# pecs_storm.net
KiCad netlist of a schematic drawn in EAGLE
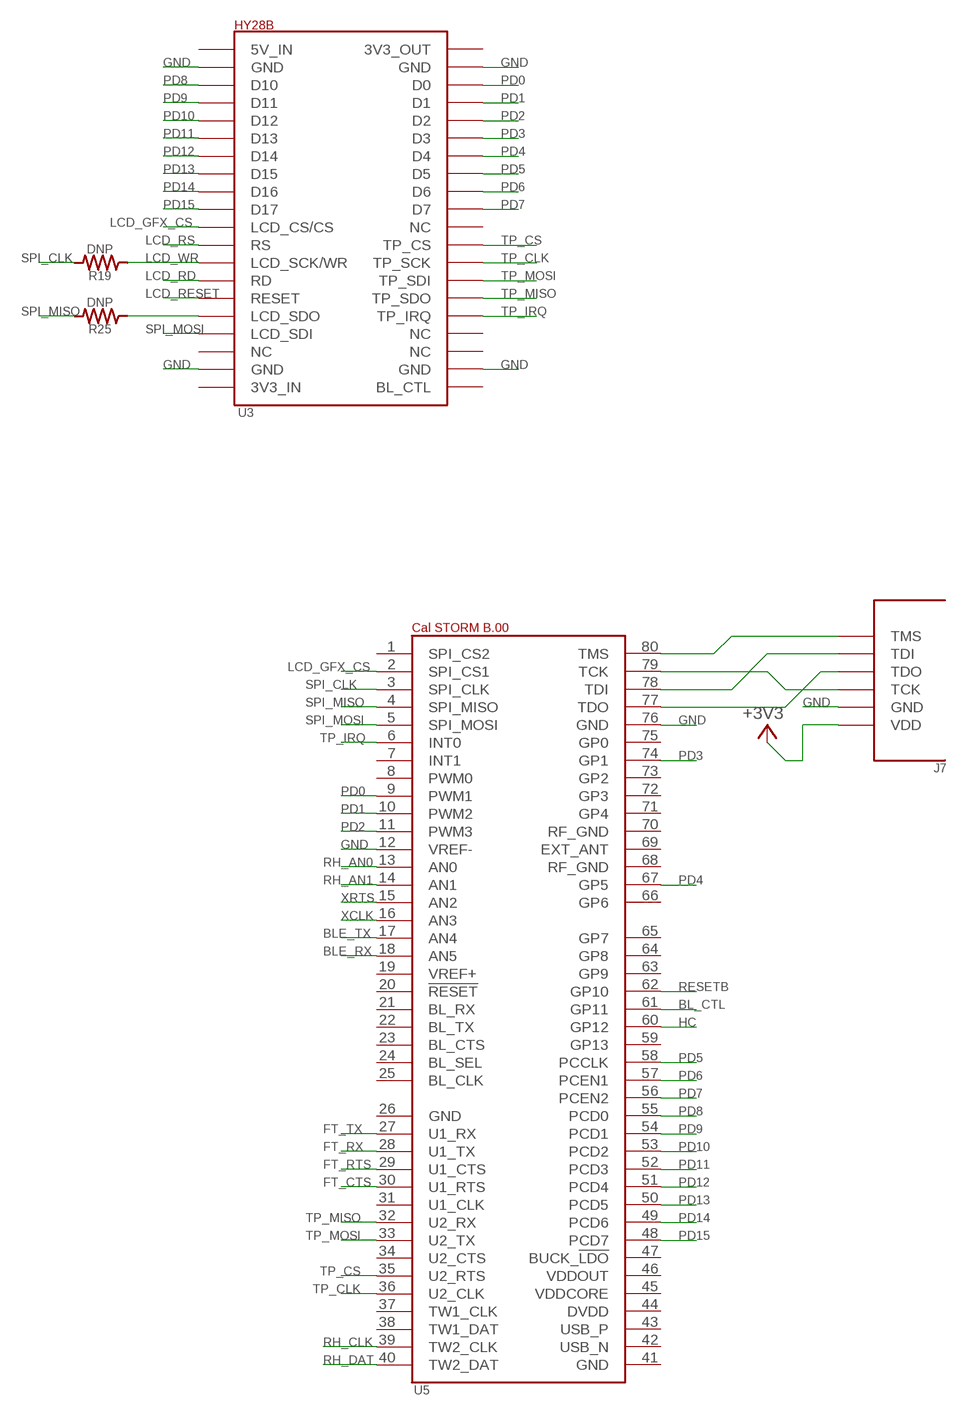
[diagram p0: schematic, sheet 1, part 1 of 2]
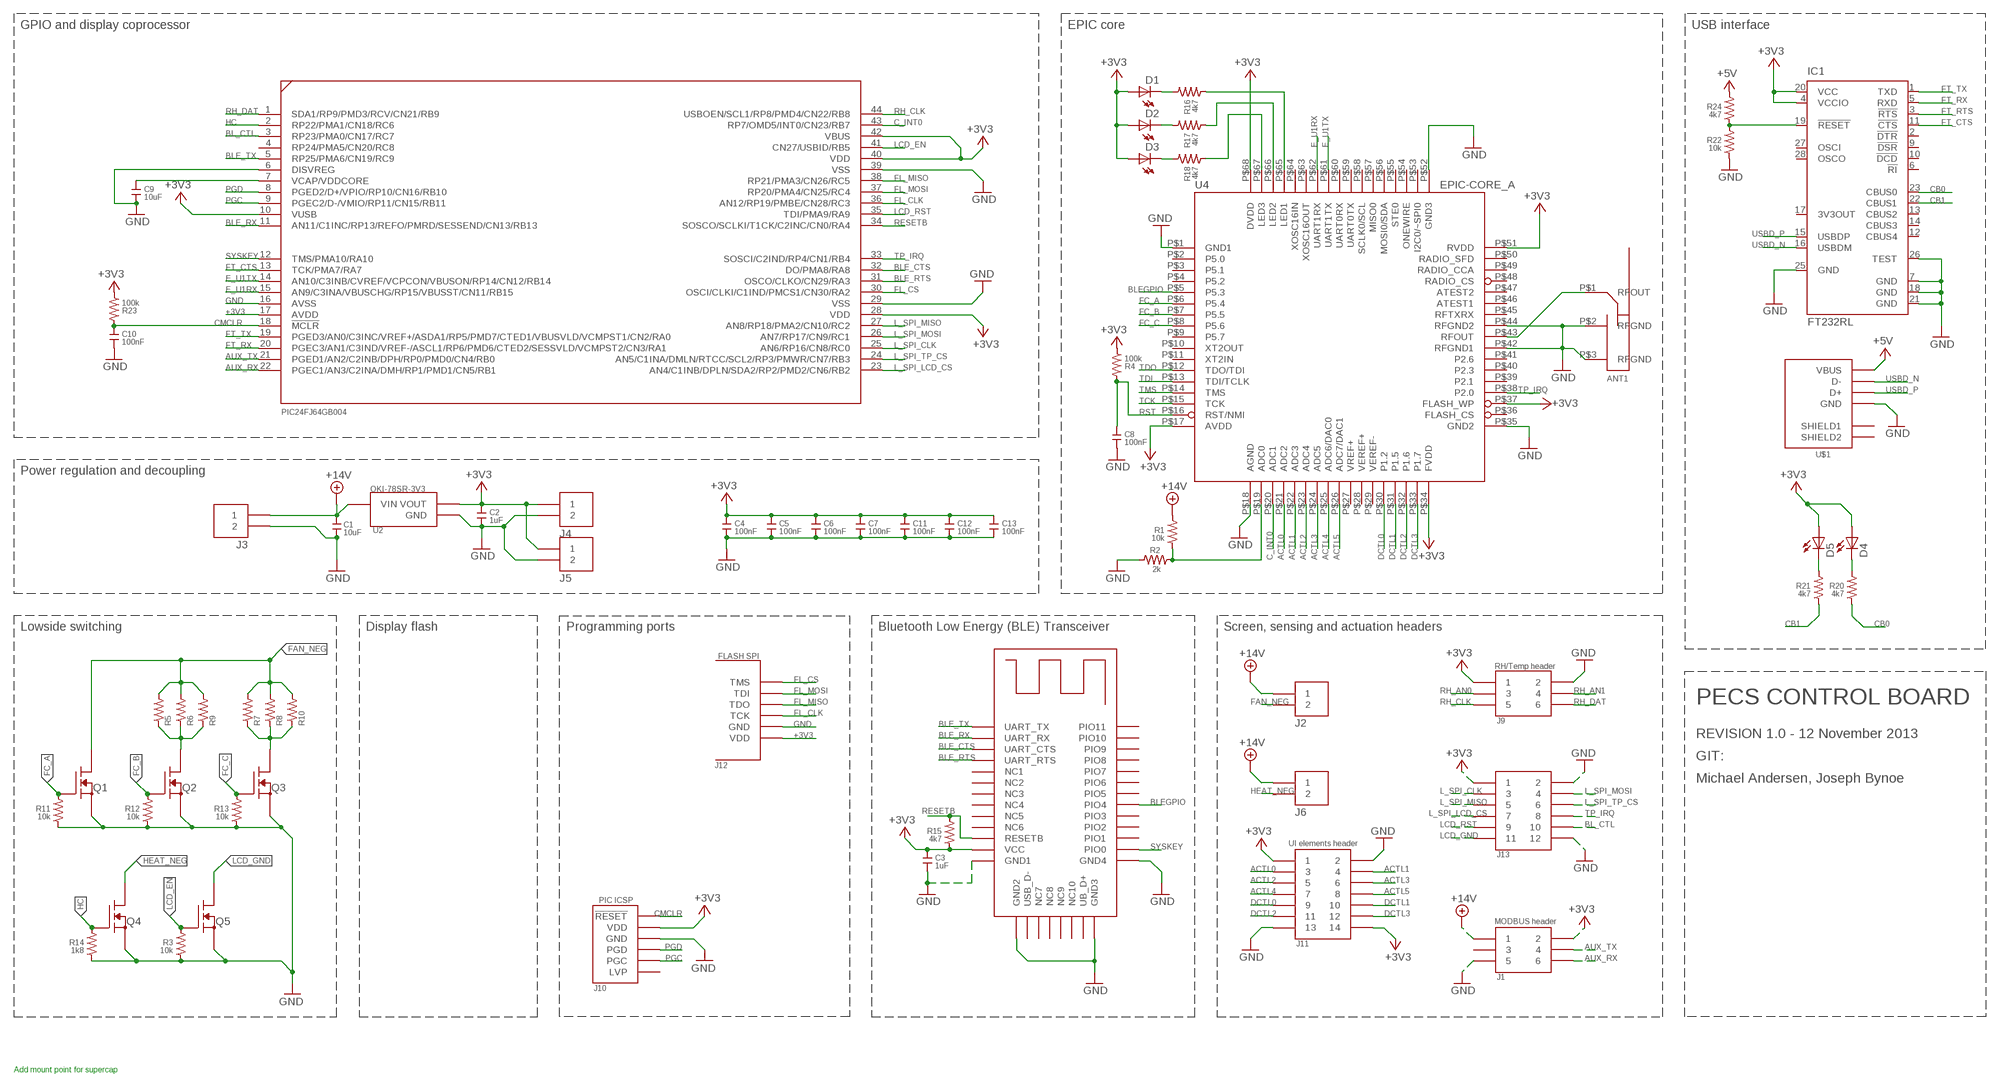
[diagram p1: schematic, sheet 1, part 2 of 2]

(export (version "E")
  (design (tool "Eeschema 10.0.6"))
  (components
    (comp (ref "ANT1")
      (value "PIFA-2.4GHZ")
      (footprint "eagle-import:PIFA-2.4GHZ")
      (libsource (lib "eagle-import") (part "PIFA-2.4GHZ"))
    )
    (comp (ref "BLE1")
      (value "HM10_BLE")
      (footprint "eagle-import:HM10")
      (libsource (lib "eagle-import") (part "HM10_BLE"))
    )
    (comp (ref "C1")
      (value "10uF")
      (footprint "eagle-import:0805")
      (libsource (lib "eagle-import") (part "0805_CAPACITOR"))
    )
    (comp (ref "C2")
      (value "1uF")
      (footprint "eagle-import:0805")
      (libsource (lib "eagle-import") (part "0805_CAPACITOR"))
    )
    (comp (ref "C3")
      (value "1uF")
      (footprint "eagle-import:0805")
      (libsource (lib "eagle-import") (part "0805_CAPACITOR"))
    )
    (comp (ref "C4")
      (value "100nF")
      (footprint "eagle-import:0805")
      (libsource (lib "eagle-import") (part "0805_CAPACITOR"))
    )
    (comp (ref "C5")
      (value "100nF")
      (footprint "eagle-import:0805")
      (libsource (lib "eagle-import") (part "0805_CAPACITOR"))
    )
    (comp (ref "C6")
      (value "100nF")
      (footprint "eagle-import:0805")
      (libsource (lib "eagle-import") (part "0805_CAPACITOR"))
    )
    (comp (ref "C7")
      (value "100nF")
      (footprint "eagle-import:0805")
      (libsource (lib "eagle-import") (part "0805_CAPACITOR"))
    )
    (comp (ref "C8")
      (value "100nF")
      (footprint "eagle-import:0805")
      (libsource (lib "eagle-import") (part "0805_CAPACITOR"))
    )
    (comp (ref "C9")
      (value "10uF")
      (footprint "eagle-import:0805")
      (libsource (lib "eagle-import") (part "0805_CAPACITOR"))
    )
    (comp (ref "C10")
      (value "100nF")
      (footprint "eagle-import:0805")
      (libsource (lib "eagle-import") (part "0805_CAPACITOR"))
    )
    (comp (ref "C11")
      (value "100nF")
      (footprint "eagle-import:0805")
      (libsource (lib "eagle-import") (part "0805_CAPACITOR"))
    )
    (comp (ref "C12")
      (value "100nF")
      (footprint "eagle-import:0805")
      (libsource (lib "eagle-import") (part "0805_CAPACITOR"))
    )
    (comp (ref "C13")
      (value "100nF")
      (footprint "eagle-import:0805")
      (libsource (lib "eagle-import") (part "0805_CAPACITOR"))
    )
    (comp (ref "D1")
      (value "LED1206")
      (footprint "eagle-import:LED-1206")
      (libsource (lib "eagle-import") (part "LED1206"))
    )
    (comp (ref "D2")
      (value "LED1206")
      (footprint "eagle-import:LED-1206")
      (libsource (lib "eagle-import") (part "LED1206"))
    )
    (comp (ref "D3")
      (value "LED1206")
      (footprint "eagle-import:LED-1206")
      (libsource (lib "eagle-import") (part "LED1206"))
    )
    (comp (ref "D4")
      (value "LED1206")
      (footprint "eagle-import:LED-1206")
      (libsource (lib "eagle-import") (part "LED1206"))
    )
    (comp (ref "D5")
      (value "LED1206")
      (footprint "eagle-import:LED-1206")
      (libsource (lib "eagle-import") (part "LED1206"))
    )
    (comp (ref "IC1")
      (value "FT232RL")
      (footprint "eagle-import:SSOP28")
      (libsource (lib "eagle-import") (part "FT232RL"))
    )
    (comp (ref "J1")
      (value "HD.1-6")
      (footprint "eagle-import:HD.1-6")
      (libsource (lib "eagle-import") (part "HD.1-6"))
    )
    (comp (ref "J2")
      (value "H.1-2")
      (footprint "eagle-import:H.1-2")
      (libsource (lib "eagle-import") (part "H.1-2"))
    )
    (comp (ref "J3")
      (value "H.1-2")
      (footprint "eagle-import:H.1-2")
      (libsource (lib "eagle-import") (part "H.1-2"))
    )
    (comp (ref "J4")
      (value "H.1-2")
      (footprint "eagle-import:H.1-2")
      (libsource (lib "eagle-import") (part "H.1-2"))
    )
    (comp (ref "J5")
      (value "H.1-2")
      (footprint "eagle-import:H.1-2")
      (libsource (lib "eagle-import") (part "H.1-2"))
    )
    (comp (ref "J6")
      (value "H.1-2")
      (footprint "eagle-import:H.1-2")
      (libsource (lib "eagle-import") (part "H.1-2"))
    )
    (comp (ref "J7")
      (value "JTAG")
      (footprint "eagle-import:JTAG")
      (libsource (lib "eagle-import") (part "JTAG"))
    )
    (comp (ref "J9")
      (value "HD.1-6")
      (footprint "eagle-import:HD.1-6")
      (libsource (lib "eagle-import") (part "HD.1-6"))
    )
    (comp (ref "J10")
      (value "ICSP_HDR")
      (footprint "eagle-import:H.1-6")
      (libsource (lib "eagle-import") (part "ICSP_HDR"))
    )
    (comp (ref "J11")
      (value "HD.1-14")
      (footprint "eagle-import:HD.1-16")
      (libsource (lib "eagle-import") (part "HD.1-14"))
    )
    (comp (ref "J12")
      (value "JTAG")
      (footprint "eagle-import:JTAG")
      (libsource (lib "eagle-import") (part "JTAG"))
    )
    (comp (ref "J13")
      (value "HD.1-12")
      (footprint "eagle-import:HD.1-12")
      (libsource (lib "eagle-import") (part "HD.1-12"))
    )
    (comp (ref "Q1")
      (value "NFET_DPAK")
      (footprint "eagle-import:DPAK")
      (libsource (lib "eagle-import") (part "NFET_DPAK"))
    )
    (comp (ref "Q2")
      (value "NFET_DPAK")
      (footprint "eagle-import:DPAK")
      (libsource (lib "eagle-import") (part "NFET_DPAK"))
    )
    (comp (ref "Q3")
      (value "NFET_DPAK")
      (footprint "eagle-import:DPAK")
      (libsource (lib "eagle-import") (part "NFET_DPAK"))
    )
    (comp (ref "Q4")
      (value "NFET_DPAK")
      (footprint "eagle-import:DPAK")
      (libsource (lib "eagle-import") (part "NFET_DPAK"))
    )
    (comp (ref "Q5")
      (value "NFET_DPAK")
      (footprint "eagle-import:DPAK")
      (libsource (lib "eagle-import") (part "NFET_DPAK"))
    )
    (comp (ref "R1")
      (value "10k")
      (footprint "eagle-import:0805")
      (libsource (lib "eagle-import") (part "0805_RESISTOR"))
    )
    (comp (ref "R2")
      (value "2k")
      (footprint "eagle-import:0805")
      (libsource (lib "eagle-import") (part "0805_RESISTOR"))
    )
    (comp (ref "R3")
      (value "10k")
      (footprint "eagle-import:0805")
      (libsource (lib "eagle-import") (part "0805_RESISTOR"))
    )
    (comp (ref "R4")
      (value "100k")
      (footprint "eagle-import:0805")
      (libsource (lib "eagle-import") (part "0805_RESISTOR"))
    )
    (comp (ref "R5")
      (value "1206_RESISTOR")
      (footprint "eagle-import:1206")
      (libsource (lib "eagle-import") (part "1206_RESISTOR"))
    )
    (comp (ref "R6")
      (value "1206_RESISTOR")
      (footprint "eagle-import:1206")
      (libsource (lib "eagle-import") (part "1206_RESISTOR"))
    )
    (comp (ref "R7")
      (value "1206_RESISTOR")
      (footprint "eagle-import:1206")
      (libsource (lib "eagle-import") (part "1206_RESISTOR"))
    )
    (comp (ref "R8")
      (value "1206_RESISTOR")
      (footprint "eagle-import:1206")
      (libsource (lib "eagle-import") (part "1206_RESISTOR"))
    )
    (comp (ref "R9")
      (value "1206_RESISTOR")
      (footprint "eagle-import:1206")
      (libsource (lib "eagle-import") (part "1206_RESISTOR"))
    )
    (comp (ref "R10")
      (value "1206_RESISTOR")
      (footprint "eagle-import:1206")
      (libsource (lib "eagle-import") (part "1206_RESISTOR"))
    )
    (comp (ref "R11")
      (value "10k")
      (footprint "eagle-import:0805")
      (libsource (lib "eagle-import") (part "0805_RESISTOR"))
    )
    (comp (ref "R12")
      (value "10k")
      (footprint "eagle-import:0805")
      (libsource (lib "eagle-import") (part "0805_RESISTOR"))
    )
    (comp (ref "R13")
      (value "10k")
      (footprint "eagle-import:0805")
      (libsource (lib "eagle-import") (part "0805_RESISTOR"))
    )
    (comp (ref "R14")
      (value "1k8")
      (footprint "eagle-import:0805")
      (libsource (lib "eagle-import") (part "0805_RESISTOR"))
    )
    (comp (ref "R15")
      (value "4k7")
      (footprint "eagle-import:0805")
      (libsource (lib "eagle-import") (part "0805_RESISTOR"))
    )
    (comp (ref "R16")
      (value "4k7")
      (footprint "eagle-import:0805")
      (libsource (lib "eagle-import") (part "0805_RESISTOR"))
    )
    (comp (ref "R17")
      (value "4k7")
      (footprint "eagle-import:0805")
      (libsource (lib "eagle-import") (part "0805_RESISTOR"))
    )
    (comp (ref "R18")
      (value "4k7")
      (footprint "eagle-import:0805")
      (libsource (lib "eagle-import") (part "0805_RESISTOR"))
    )
    (comp (ref "R19")
      (value "DNP")
      (footprint "eagle-import:0805")
      (libsource (lib "eagle-import") (part "0805_RESISTOR"))
    )
    (comp (ref "R20")
      (value "4k7")
      (footprint "eagle-import:0805")
      (libsource (lib "eagle-import") (part "0805_RESISTOR"))
    )
    (comp (ref "R21")
      (value "4k7")
      (footprint "eagle-import:0805")
      (libsource (lib "eagle-import") (part "0805_RESISTOR"))
    )
    (comp (ref "R22")
      (value "10k")
      (footprint "eagle-import:0805")
      (libsource (lib "eagle-import") (part "0805_RESISTOR"))
    )
    (comp (ref "R23")
      (value "100k")
      (footprint "eagle-import:0805")
      (libsource (lib "eagle-import") (part "0805_RESISTOR"))
    )
    (comp (ref "R24")
      (value "4k7")
      (footprint "eagle-import:0805")
      (libsource (lib "eagle-import") (part "0805_RESISTOR"))
    )
    (comp (ref "R25")
      (value "DNP")
      (footprint "eagle-import:0805")
      (libsource (lib "eagle-import") (part "0805_RESISTOR"))
    )
    (comp (ref "U$1")
      (value "USB_B")
      (footprint "eagle-import:USB_MOLEX_7041")
      (libsource (lib "eagle-import") (part "USB_B"))
    )
    (comp (ref "U1")
      (value "PIC24FJ32GB004")
      (footprint "eagle-import:TQFP44")
      (libsource (lib "eagle-import") (part "PIC24FJ32GB004"))
    )
    (comp (ref "U2")
      (value "OKI-78SR_3V3_SMPS")
      (footprint "eagle-import:SMPS_MODULE")
      (libsource (lib "eagle-import") (part "OKI-78SR_3V3_SMPS"))
    )
    (comp (ref "U3")
      (value "HY28B")
      (footprint "eagle-import:SCREEN")
      (libsource (lib "eagle-import") (part "HY28B"))
    )
    (comp (ref "U4")
      (value "EPIC-CORE_A")
      (footprint "eagle-import:EPIC-LCC68")
      (libsource (lib "eagle-import") (part "EPIC-CORE_A"))
    )
    (comp (ref "U5")
      (value "STORM_B.00")
      (footprint "eagle-import:STORM_LANDING")
      (libsource (lib "eagle-import") (part "STORM_B.00"))
    )
  )
  (nets
    (net (code "1") (name "+3V3") (class "Default")
      (node (ref "BLE1") (pin "P$12") (pinfunction "VCC_P$12") (pintype "power_in"))
      (node (ref "C11") (pin "2") (pinfunction "P$2_2") (pintype "passive"))
      (node (ref "C12") (pin "2") (pinfunction "P$2_2") (pintype "passive"))
      (node (ref "C13") (pin "2") (pinfunction "P$2_2") (pintype "passive"))
      (node (ref "C2") (pin "2") (pinfunction "P$2_2") (pintype "passive"))
      (node (ref "C3") (pin "2") (pinfunction "P$2_2") (pintype "passive"))
      (node (ref "C4") (pin "2") (pinfunction "P$2_2") (pintype "passive"))
      (node (ref "C5") (pin "2") (pinfunction "P$2_2") (pintype "passive"))
      (node (ref "C6") (pin "2") (pinfunction "P$2_2") (pintype "passive"))
      (node (ref "C7") (pin "2") (pinfunction "P$2_2") (pintype "passive"))
      (node (ref "D1") (pin "A") (pinfunction "A_A") (pintype "passive"))
      (node (ref "D2") (pin "A") (pinfunction "A_A") (pintype "passive"))
      (node (ref "D3") (pin "A") (pinfunction "A_A") (pintype "passive"))
      (node (ref "D4") (pin "A") (pinfunction "A_A") (pintype "passive"))
      (node (ref "D5") (pin "A") (pinfunction "A_A") (pintype "passive"))
      (node (ref "IC1") (pin "20") (pinfunction "VCC_20") (pintype "power_in"))
      (node (ref "IC1") (pin "4") (pinfunction "VCCIO_4") (pintype "power_in"))
      (node (ref "J1") (pin "P2") (pinfunction "2_P2") (pintype "bidirectional"))
      (node (ref "J10") (pin "P2") (pinfunction "VDD_P2") (pintype "bidirectional"))
      (node (ref "J11") (pin "P1") (pinfunction "1_P1") (pintype "bidirectional"))
      (node (ref "J11") (pin "P14") (pinfunction "14_P14") (pintype "bidirectional"))
      (node (ref "J12") (pin "VDD") (pinfunction "VDD_VDD") (pintype "bidirectional"))
      (node (ref "J13") (pin "P1") (pinfunction "1_P1") (pintype "bidirectional"))
      (node (ref "J4") (pin "P1") (pinfunction "1_P1") (pintype "bidirectional"))
      (node (ref "J5") (pin "P1") (pinfunction "1_P1") (pintype "bidirectional"))
      (node (ref "J7") (pin "VDD") (pinfunction "VDD_VDD") (pintype "bidirectional"))
      (node (ref "J9") (pin "P1") (pinfunction "1_P1") (pintype "bidirectional"))
      (node (ref "R15") (pin "1") (pinfunction "P$1_1") (pintype "passive"))
      (node (ref "R23") (pin "1") (pinfunction "P$1_1") (pintype "passive"))
      (node (ref "R4") (pin "1") (pinfunction "P$1_1") (pintype "passive"))
      (node (ref "U1") (pin "10") (pinfunction "VUSB_10") (pintype "bidirectional"))
      (node (ref "U1") (pin "17") (pinfunction "AVDD_17") (pintype "bidirectional"))
      (node (ref "U1") (pin "28") (pinfunction "VDD_28") (pintype "bidirectional"))
      (node (ref "U1") (pin "40") (pinfunction "VDD_40") (pintype "bidirectional"))
      (node (ref "U1") (pin "42") (pinfunction "VBUS_42") (pintype "bidirectional"))
      (node (ref "U2") (pin "VOUT") (pinfunction "VOUT_VOUT") (pintype "power_in"))
      (node (ref "U4") (pin "P$17") (pinfunction "AVDD_P$17") (pintype "bidirectional"))
      (node (ref "U4") (pin "P$34") (pinfunction "FVDD_P$34") (pintype "bidirectional"))
      (node (ref "U4") (pin "P$37") (pinfunction "FLASH_WP_P$37") (pintype "bidirectional"))
      (node (ref "U4") (pin "P$51") (pinfunction "RVDD_P$51") (pintype "bidirectional"))
      (node (ref "U4") (pin "P$68") (pinfunction "DVDD_P$68") (pintype "bidirectional"))
    )
    (net (code "2") (name "+5V") (class "Default")
      (node (ref "R24") (pin "2") (pinfunction "P$2_2") (pintype "passive"))
      (node (ref "U$1") (pin "1_VBUS") (pinfunction "VBUS_1_VBUS") (pintype "bidirectional"))
    )
    (net (code "3") (name "+14V") (class "Default")
      (node (ref "C1") (pin "2") (pinfunction "P$2_2") (pintype "passive"))
      (node (ref "J1") (pin "P1") (pinfunction "1_P1") (pintype "bidirectional"))
      (node (ref "J2") (pin "P1") (pinfunction "1_P1") (pintype "bidirectional"))
      (node (ref "J3") (pin "P1") (pinfunction "1_P1") (pintype "bidirectional"))
      (node (ref "J6") (pin "P1") (pinfunction "1_P1") (pintype "bidirectional"))
      (node (ref "R1") (pin "2") (pinfunction "P$2_2") (pintype "passive"))
      (node (ref "U2") (pin "VIN") (pinfunction "VIN_VIN") (pintype "power_in"))
    )
    (net (code "4") (name "/ACTL0") (class "Default")
      (node (ref "J11") (pin "P3") (pinfunction "3_P3") (pintype "bidirectional"))
      (node (ref "U4") (pin "P$21") (pinfunction "ADC2_P$21") (pintype "bidirectional"))
    )
    (net (code "5") (name "/ACTL1") (class "Default")
      (node (ref "J11") (pin "P4") (pinfunction "4_P4") (pintype "bidirectional"))
      (node (ref "U4") (pin "P$22") (pinfunction "ADC3_P$22") (pintype "bidirectional"))
    )
    (net (code "6") (name "/ACTL2") (class "Default")
      (node (ref "J11") (pin "P5") (pinfunction "5_P5") (pintype "bidirectional"))
      (node (ref "U4") (pin "P$23") (pinfunction "ADC4_P$23") (pintype "bidirectional"))
    )
    (net (code "7") (name "/ACTL3") (class "Default")
      (node (ref "J11") (pin "P6") (pinfunction "6_P6") (pintype "bidirectional"))
      (node (ref "U4") (pin "P$24") (pinfunction "ADC5_P$24") (pintype "bidirectional"))
    )
    (net (code "8") (name "/ACTL4") (class "Default")
      (node (ref "J11") (pin "P7") (pinfunction "7_P7") (pintype "bidirectional"))
      (node (ref "U4") (pin "P$25") (pinfunction "ADC6/DAC0_P$25") (pintype "bidirectional"))
    )
    (net (code "9") (name "/ACTL5") (class "Default")
      (node (ref "J11") (pin "P8") (pinfunction "8_P8") (pintype "bidirectional"))
      (node (ref "U4") (pin "P$26") (pinfunction "ADC7/DAC1_P$26") (pintype "bidirectional"))
    )
    (net (code "10") (name "/AUX_RX") (class "Default")
      (node (ref "J1") (pin "P6") (pinfunction "6_P6") (pintype "bidirectional"))
      (node (ref "U1") (pin "22") (pinfunction "PGEC1/AN3/C2INA/DMH/RP1/PMD1/CN5/RB1_22") (pintype "bidirectional"))
    )
    (net (code "11") (name "/AUX_TX") (class "Default")
      (node (ref "J1") (pin "P4") (pinfunction "4_P4") (pintype "bidirectional"))
      (node (ref "U1") (pin "21") (pinfunction "PGED1/AN2/C2INB/DPH/RP0/PMD0/CN4/RB0_21") (pintype "bidirectional"))
    )
    (net (code "12") (name "/BLEGPIO") (class "Default")
      (node (ref "BLE1") (pin "P$27") (pinfunction "PIO4_P$27") (pintype "bidirectional"))
      (node (ref "U4") (pin "P$5") (pinfunction "P5.3_P$5") (pintype "bidirectional"))
    )
    (net (code "13") (name "/BLE_CTS") (class "Default")
      (node (ref "BLE1") (pin "P$3") (pinfunction "UART_CTS_P$3") (pintype "bidirectional"))
      (node (ref "U1") (pin "32") (pinfunction "DO/PMA8/RA8_32") (pintype "bidirectional"))
    )
    (net (code "14") (name "/BLE_RTS") (class "Default")
      (node (ref "BLE1") (pin "P$4") (pinfunction "UART_RTS_P$4") (pintype "bidirectional"))
      (node (ref "U1") (pin "31") (pinfunction "OSCO/CLKO/CN29/RA3_31") (pintype "bidirectional"))
    )
    (net (code "15") (name "/BLE_RX") (class "Default")
      (node (ref "BLE1") (pin "P$2") (pinfunction "UART_RX_P$2") (pintype "bidirectional"))
      (node (ref "U1") (pin "11") (pinfunction "AN11/C1INC/RP13/REFO/PMRD/SESSEND/CN13/RB13_11") (pintype "bidirectional"))
      (node (ref "U5") (pin "18") (pinfunction "AN5_18") (pintype "bidirectional"))
    )
    (net (code "16") (name "/BLE_TX") (class "Default")
      (node (ref "BLE1") (pin "P$1") (pinfunction "UART_TX_P$1") (pintype "bidirectional"))
      (node (ref "U1") (pin "5") (pinfunction "RP25/PMA6/CN19/RC9_5") (pintype "bidirectional"))
      (node (ref "U5") (pin "17") (pinfunction "AN4_17") (pintype "bidirectional"))
    )
    (net (code "17") (name "/BL_CTL") (class "Default")
      (node (ref "J13") (pin "P10") (pinfunction "10_P10") (pintype "bidirectional"))
      (node (ref "U1") (pin "3") (pinfunction "RP23/PMA0/CN17/RC7_3") (pintype "bidirectional"))
      (node (ref "U5") (pin "61") (pinfunction "GP11_61") (pintype "bidirectional"))
    )
    (net (code "18") (name "/CB0") (class "Default")
      (node (ref "IC1") (pin "23") (pinfunction "CBUS0_23") (pintype "bidirectional"))
      (node (ref "R20") (pin "1") (pinfunction "P$1_1") (pintype "passive"))
    )
    (net (code "19") (name "/CB1") (class "Default")
      (node (ref "IC1") (pin "22") (pinfunction "CBUS1_22") (pintype "bidirectional"))
      (node (ref "R21") (pin "1") (pinfunction "P$1_1") (pintype "passive"))
    )
    (net (code "20") (name "/CMCLR") (class "Default")
      (node (ref "C10") (pin "2") (pinfunction "P$2_2") (pintype "passive"))
      (node (ref "J10") (pin "P1") (pinfunction "~{RESET}_P1") (pintype "bidirectional"))
      (node (ref "R23") (pin "2") (pinfunction "P$2_2") (pintype "passive"))
      (node (ref "U1") (pin "18") (pinfunction "~{MCLR}_18") (pintype "bidirectional"))
    )
    (net (code "21") (name "/C_INT0") (class "Default")
      (node (ref "U1") (pin "43") (pinfunction "RP7/OMD5/INT0/CN23/RB7_43") (pintype "bidirectional"))
      (node (ref "U4") (pin "P$20") (pinfunction "ADC1_P$20") (pintype "bidirectional"))
    )
    (net (code "22") (name "/DCTL0") (class "Default")
      (node (ref "J11") (pin "P9") (pinfunction "9_P9") (pintype "bidirectional"))
      (node (ref "U4") (pin "P$30") (pinfunction "P1.2_P$30") (pintype "bidirectional"))
    )
    (net (code "23") (name "/DCTL1") (class "Default")
      (node (ref "J11") (pin "P10") (pinfunction "10_P10") (pintype "bidirectional"))
      (node (ref "U4") (pin "P$31") (pinfunction "P1.5_P$31") (pintype "bidirectional"))
    )
    (net (code "24") (name "/DCTL2") (class "Default")
      (node (ref "J11") (pin "P11") (pinfunction "11_P11") (pintype "bidirectional"))
      (node (ref "U4") (pin "P$32") (pinfunction "P1.6_P$32") (pintype "bidirectional"))
    )
    (net (code "25") (name "/DCTL3") (class "Default")
      (node (ref "J11") (pin "P12") (pinfunction "12_P12") (pintype "bidirectional"))
      (node (ref "U4") (pin "P$33") (pinfunction "P1.7_P$33") (pintype "bidirectional"))
    )
    (net (code "26") (name "/E_U1RX") (class "Default")
      (node (ref "U1") (pin "15") (pinfunction "AN9/C3INA/VBUSCHG/RP15/VBUSST/CN11/RB15_15") (pintype "bidirectional"))
      (node (ref "U4") (pin "P$62") (pinfunction "UART1RX_P$62") (pintype "bidirectional"))
    )
    (net (code "27") (name "/E_U1TX") (class "Default")
      (node (ref "U1") (pin "14") (pinfunction "AN10/C3INB/CVREF/VCPCON/VBUSON/RP14/CN12/RB14_14") (pintype "bidirectional"))
      (node (ref "U4") (pin "P$61") (pinfunction "UART1TX_P$61") (pintype "bidirectional"))
    )
    (net (code "28") (name "/FL_CLK") (class "Default")
      (node (ref "J12") (pin "TCK") (pinfunction "TCK_TCK") (pintype "bidirectional"))
      (node (ref "U1") (pin "36") (pinfunction "AN12/RP19/PMBE/CN28/RC3_36") (pintype "bidirectional"))
    )
    (net (code "29") (name "/FL_CS") (class "Default")
      (node (ref "J12") (pin "TMS") (pinfunction "TMS_TMS") (pintype "bidirectional"))
      (node (ref "U1") (pin "30") (pinfunction "OSCI/CLKI/C1IND/PMCS1/CN30/RA2_30") (pintype "bidirectional"))
    )
    (net (code "30") (name "/FL_MISO") (class "Default")
      (node (ref "J12") (pin "TDO") (pinfunction "TDO_TDO") (pintype "bidirectional"))
      (node (ref "U1") (pin "38") (pinfunction "RP21/PMA3/CN26/RC5_38") (pintype "bidirectional"))
    )
    (net (code "31") (name "/FL_MOSI") (class "Default")
      (node (ref "J12") (pin "TDI") (pinfunction "TDI_TDI") (pintype "bidirectional"))
      (node (ref "U1") (pin "37") (pinfunction "RP20/PMA4/CN25/RC4_37") (pintype "bidirectional"))
    )
    (net (code "32") (name "/FT_CTS") (class "Default")
      (node (ref "IC1") (pin "11") (pinfunction "~{CTS}_11") (pintype "input"))
      (node (ref "U1") (pin "13") (pinfunction "TCK/PMA7/RA7_13") (pintype "bidirectional"))
      (node (ref "U5") (pin "30") (pinfunction "U1_RTS_30") (pintype "bidirectional"))
    )
    (net (code "33") (name "/FT_RTS") (class "Default")
      (node (ref "IC1") (pin "3") (pinfunction "~{RTS}_3") (pintype "output"))
      (node (ref "U5") (pin "29") (pinfunction "U1_CTS_29") (pintype "bidirectional"))
    )
    (net (code "34") (name "/FT_RX") (class "Default")
      (node (ref "IC1") (pin "5") (pinfunction "RXD_5") (pintype "input"))
      (node (ref "U1") (pin "20") (pinfunction "PGEC3/AN1/C3IND/VREF-/ASCL1/RP6/PMD6/CTED2/SESSVLD/VCMPST2/CN3/RA1_20") (pintype "bidirectional"))
      (node (ref "U5") (pin "28") (pinfunction "U1_TX_28") (pintype "bidirectional"))
    )
    (net (code "35") (name "/FT_TX") (class "Default")
      (node (ref "IC1") (pin "1") (pinfunction "TXD_1") (pintype "output"))
      (node (ref "U1") (pin "19") (pinfunction "PGED3/AN0/C3INC/VREF+/ASDA1/RP5/PMD7/CTED1/VBUSVLD/VCMPST1/CN2/RA0_19") (pintype "bidirectional"))
      (node (ref "U5") (pin "27") (pinfunction "U1_RX_27") (pintype "bidirectional"))
    )
    (net (code "36") (name "/LCD_GFX_CS") (class "Default")
      (node (ref "U3") (pin "P$11") (pinfunction "LCD_CS/CS_P$11") (pintype "bidirectional"))
      (node (ref "U5") (pin "2") (pinfunction "SPI_CS1_2") (pintype "bidirectional"))
    )
    (net (code "37") (name "/LCD_RD") (class "Default")
      (node (ref "U3") (pin "P$14") (pinfunction "RD_P$14") (pintype "bidirectional"))
    )
    (net (code "38") (name "/LCD_RESET") (class "Default")
      (node (ref "U3") (pin "P$15") (pinfunction "RESET_P$15") (pintype "bidirectional"))
    )
    (net (code "39") (name "/LCD_RS") (class "Default")
      (node (ref "U3") (pin "P$12") (pinfunction "RS_P$12") (pintype "bidirectional"))
    )
    (net (code "40") (name "/LCD_RST") (class "Default")
      (node (ref "J13") (pin "P9") (pinfunction "9_P9") (pintype "bidirectional"))
      (node (ref "U1") (pin "35") (pinfunction "TDI/PMA9/RA9_35") (pintype "bidirectional"))
    )
    (net (code "41") (name "/LCD_WR") (class "Default")
      (node (ref "R19") (pin "2") (pinfunction "P$2_2") (pintype "passive"))
      (node (ref "U3") (pin "P$13") (pinfunction "LCD_SCK/WR_P$13") (pintype "bidirectional"))
    )
    (net (code "42") (name "/L_SPI_CLK") (class "Default")
      (node (ref "J13") (pin "P3") (pinfunction "3_P3") (pintype "bidirectional"))
      (node (ref "U1") (pin "25") (pinfunction "AN6/RP16/CN8/RC0_25") (pintype "bidirectional"))
    )
    (net (code "43") (name "/L_SPI_LCD_CS") (class "Default")
      (node (ref "J13") (pin "P7") (pinfunction "7_P7") (pintype "bidirectional"))
      (node (ref "U1") (pin "23") (pinfunction "AN4/C1INB/DPLN/SDA2/RP2/PMD2/CN6/RB2_23") (pintype "bidirectional"))
    )
    (net (code "44") (name "/L_SPI_MISO") (class "Default")
      (node (ref "J13") (pin "P5") (pinfunction "5_P5") (pintype "bidirectional"))
      (node (ref "U1") (pin "27") (pinfunction "AN8/RP18/PMA2/CN10/RC2_27") (pintype "bidirectional"))
    )
    (net (code "45") (name "/L_SPI_MOSI") (class "Default")
      (node (ref "J13") (pin "P4") (pinfunction "4_P4") (pintype "bidirectional"))
      (node (ref "U1") (pin "26") (pinfunction "AN7/RP17/CN9/RC1_26") (pintype "bidirectional"))
    )
    (net (code "46") (name "/L_SPI_TP_CS") (class "Default")
      (node (ref "J13") (pin "P6") (pinfunction "6_P6") (pintype "bidirectional"))
      (node (ref "U1") (pin "24") (pinfunction "AN5/C1INA/DMLN/RTCC/SCL2/RP3/PMWR/CN7/RB3_24") (pintype "bidirectional"))
    )
    (net (code "47") (name "/PD0") (class "Default")
      (node (ref "U3") (pin "P$38") (pinfunction "D0_P$38") (pintype "bidirectional"))
      (node (ref "U5") (pin "9") (pinfunction "PWM1_9") (pintype "bidirectional"))
    )
    (net (code "48") (name "/PD1") (class "Default")
      (node (ref "U3") (pin "P$37") (pinfunction "D1_P$37") (pintype "bidirectional"))
      (node (ref "U5") (pin "10") (pinfunction "PWM2_10") (pintype "bidirectional"))
    )
    (net (code "49") (name "/PD2") (class "Default")
      (node (ref "U3") (pin "P$36") (pinfunction "D2_P$36") (pintype "bidirectional"))
      (node (ref "U5") (pin "11") (pinfunction "PWM3_11") (pintype "bidirectional"))
    )
    (net (code "50") (name "/PD3") (class "Default")
      (node (ref "U3") (pin "P$35") (pinfunction "D3_P$35") (pintype "bidirectional"))
      (node (ref "U5") (pin "74") (pinfunction "GP1_74") (pintype "bidirectional"))
    )
    (net (code "51") (name "/PD4") (class "Default")
      (node (ref "U3") (pin "P$34") (pinfunction "D4_P$34") (pintype "bidirectional"))
      (node (ref "U5") (pin "67") (pinfunction "GP5_67") (pintype "bidirectional"))
    )
    (net (code "52") (name "/PD5") (class "Default")
      (node (ref "U3") (pin "P$33") (pinfunction "D5_P$33") (pintype "bidirectional"))
      (node (ref "U5") (pin "58") (pinfunction "PCCLK_58") (pintype "bidirectional"))
    )
    (net (code "53") (name "/PD6") (class "Default")
      (node (ref "U3") (pin "P$32") (pinfunction "D6_P$32") (pintype "bidirectional"))
      (node (ref "U5") (pin "57") (pinfunction "PCEN1_57") (pintype "bidirectional"))
    )
    (net (code "54") (name "/PD7") (class "Default")
      (node (ref "U3") (pin "P$31") (pinfunction "D7_P$31") (pintype "bidirectional"))
      (node (ref "U5") (pin "56") (pinfunction "PCEN2_56") (pintype "bidirectional"))
    )
    (net (code "55") (name "/PD8") (class "Default")
      (node (ref "U3") (pin "P$3") (pinfunction "D10_P$3") (pintype "bidirectional"))
      (node (ref "U5") (pin "55") (pinfunction "PCD0_55") (pintype "bidirectional"))
    )
    (net (code "56") (name "/PD9") (class "Default")
      (node (ref "U3") (pin "P$4") (pinfunction "D11_P$4") (pintype "bidirectional"))
      (node (ref "U5") (pin "54") (pinfunction "PCD1_54") (pintype "bidirectional"))
    )
    (net (code "57") (name "/PD10") (class "Default")
      (node (ref "U3") (pin "P$5") (pinfunction "D12_P$5") (pintype "bidirectional"))
      (node (ref "U5") (pin "53") (pinfunction "PCD2_53") (pintype "bidirectional"))
    )
    (net (code "58") (name "/PD11") (class "Default")
      (node (ref "U3") (pin "P$6") (pinfunction "D13_P$6") (pintype "bidirectional"))
      (node (ref "U5") (pin "52") (pinfunction "PCD3_52") (pintype "bidirectional"))
    )
    (net (code "59") (name "/PD12") (class "Default")
      (node (ref "U3") (pin "P$7") (pinfunction "D14_P$7") (pintype "bidirectional"))
      (node (ref "U5") (pin "51") (pinfunction "PCD4_51") (pintype "bidirectional"))
    )
    (net (code "60") (name "/PD13") (class "Default")
      (node (ref "U3") (pin "P$8") (pinfunction "D15_P$8") (pintype "bidirectional"))
      (node (ref "U5") (pin "50") (pinfunction "PCD5_50") (pintype "bidirectional"))
    )
    (net (code "61") (name "/PD14") (class "Default")
      (node (ref "U3") (pin "P$9") (pinfunction "D16_P$9") (pintype "bidirectional"))
      (node (ref "U5") (pin "49") (pinfunction "PCD6_49") (pintype "bidirectional"))
    )
    (net (code "62") (name "/PD15") (class "Default")
      (node (ref "U3") (pin "P$10") (pinfunction "D17_P$10") (pintype "bidirectional"))
      (node (ref "U5") (pin "48") (pinfunction "PCD7_48") (pintype "bidirectional"))
    )
    (net (code "63") (name "/PGC") (class "Default")
      (node (ref "J10") (pin "P5") (pinfunction "PGC_P5") (pintype "bidirectional"))
      (node (ref "U1") (pin "9") (pinfunction "PGEC2/D-/VMIO/RP11/CN15/RB11_9") (pintype "bidirectional"))
    )
    (net (code "64") (name "/PGD") (class "Default")
      (node (ref "J10") (pin "P4") (pinfunction "PGD_P4") (pintype "bidirectional"))
      (node (ref "U1") (pin "8") (pinfunction "PGED2/D+/VPIO/RP10/CN16/RB10_8") (pintype "bidirectional"))
    )
    (net (code "65") (name "/RESETB") (class "Default")
      (node (ref "BLE1") (pin "P$11") (pinfunction "RESETB_P$11") (pintype "input"))
      (node (ref "R15") (pin "2") (pinfunction "P$2_2") (pintype "passive"))
      (node (ref "U1") (pin "34") (pinfunction "SOSCO/SCLKI/T1CK/C2INC/CN0/RA4_34") (pintype "bidirectional"))
      (node (ref "U5") (pin "62") (pinfunction "GP10_62") (pintype "bidirectional"))
    )
    (net (code "66") (name "/RH_AN0") (class "Default")
      (node (ref "J9") (pin "P3") (pinfunction "3_P3") (pintype "bidirectional"))
      (node (ref "U5") (pin "13") (pinfunction "AN0_13") (pintype "bidirectional"))
    )
    (net (code "67") (name "/RH_AN1") (class "Default")
      (node (ref "J9") (pin "P4") (pinfunction "4_P4") (pintype "bidirectional"))
      (node (ref "U5") (pin "14") (pinfunction "AN1_14") (pintype "bidirectional"))
    )
    (net (code "68") (name "/RH_CLK") (class "Default")
      (node (ref "J9") (pin "P5") (pinfunction "5_P5") (pintype "bidirectional"))
      (node (ref "U1") (pin "44") (pinfunction "USBOEN/SCL1/RP8/PMD4/CN22/RB8_44") (pintype "bidirectional"))
      (node (ref "U5") (pin "39") (pinfunction "TW2_CLK_39") (pintype "bidirectional"))
    )
    (net (code "69") (name "/RH_DAT") (class "Default")
      (node (ref "J9") (pin "P6") (pinfunction "6_P6") (pintype "bidirectional"))
      (node (ref "U1") (pin "1") (pinfunction "SDA1/RP9/PMD3/RCV/CN21/RB9_1") (pintype "bidirectional"))
      (node (ref "U5") (pin "40") (pinfunction "TW2_DAT_40") (pintype "bidirectional"))
    )
    (net (code "70") (name "/RST") (class "Default")
      (node (ref "C8") (pin "2") (pinfunction "P$2_2") (pintype "passive"))
      (node (ref "R4") (pin "2") (pinfunction "P$2_2") (pintype "passive"))
      (node (ref "U4") (pin "P$16") (pinfunction "RST/NMI_P$16") (pintype "bidirectional"))
    )
    (net (code "71") (name "/SPI_CLK") (class "Default")
      (node (ref "R19") (pin "1") (pinfunction "P$1_1") (pintype "passive"))
      (node (ref "U5") (pin "3") (pinfunction "SPI_CLK_3") (pintype "bidirectional"))
    )
    (net (code "72") (name "/SPI_MISO") (class "Default")
      (node (ref "R25") (pin "1") (pinfunction "P$1_1") (pintype "passive"))
      (node (ref "U5") (pin "4") (pinfunction "SPI_MISO_4") (pintype "bidirectional"))
    )
    (net (code "73") (name "/SPI_MOSI") (class "Default")
      (node (ref "U3") (pin "P$17") (pinfunction "LCD_SDI_P$17") (pintype "bidirectional"))
      (node (ref "U5") (pin "5") (pinfunction "SPI_MOSI_5") (pintype "bidirectional"))
    )
    (net (code "74") (name "/SYSKEY") (class "Default")
      (node (ref "BLE1") (pin "P$23") (pinfunction "PIO0_P$23") (pintype "bidirectional"))
      (node (ref "U1") (pin "12") (pinfunction "TMS/PMA10/RA10_12") (pintype "bidirectional"))
    )
    (net (code "75") (name "/TCK") (class "Default")
      (node (ref "U4") (pin "P$15") (pinfunction "TCK_P$15") (pintype "bidirectional"))
    )
    (net (code "76") (name "/TDI") (class "Default")
      (node (ref "U4") (pin "P$13") (pinfunction "TDI/TCLK_P$13") (pintype "bidirectional"))
    )
    (net (code "77") (name "/TDO") (class "Default")
      (node (ref "U4") (pin "P$12") (pinfunction "TDO/TDI_P$12") (pintype "bidirectional"))
    )
    (net (code "78") (name "/TMS") (class "Default")
      (node (ref "U4") (pin "P$14") (pinfunction "TMS_P$14") (pintype "bidirectional"))
    )
    (net (code "79") (name "/TP_CLK") (class "Default")
      (node (ref "U3") (pin "P$28") (pinfunction "TP_SCK_P$28") (pintype "bidirectional"))
      (node (ref "U5") (pin "36") (pinfunction "U2_CLK_36") (pintype "bidirectional"))
    )
    (net (code "80") (name "/TP_CS") (class "Default")
      (node (ref "U3") (pin "P$29") (pinfunction "TP_CS_P$29") (pintype "bidirectional"))
      (node (ref "U5") (pin "35") (pinfunction "U2_RTS_35") (pintype "bidirectional"))
    )
    (net (code "81") (name "/TP_IRQ") (class "Default")
      (node (ref "J13") (pin "P8") (pinfunction "8_P8") (pintype "bidirectional"))
      (node (ref "U1") (pin "33") (pinfunction "SOSCI/C2IND/RP4/CN1/RB4_33") (pintype "bidirectional"))
      (node (ref "U3") (pin "P$25") (pinfunction "TP_IRQ_P$25") (pintype "bidirectional"))
      (node (ref "U4") (pin "P$38") (pinfunction "P2.0_P$38") (pintype "bidirectional"))
      (node (ref "U5") (pin "6") (pinfunction "INT0_6") (pintype "bidirectional"))
    )
    (net (code "82") (name "/TP_MISO") (class "Default")
      (node (ref "U3") (pin "P$26") (pinfunction "TP_SDO_P$26") (pintype "bidirectional"))
      (node (ref "U5") (pin "32") (pinfunction "U2_RX_32") (pintype "bidirectional"))
    )
    (net (code "83") (name "/TP_MOSI") (class "Default")
      (node (ref "U3") (pin "P$27") (pinfunction "TP_SDI_P$27") (pintype "bidirectional"))
      (node (ref "U5") (pin "33") (pinfunction "U2_TX_33") (pintype "bidirectional"))
    )
    (net (code "84") (name "/USBD_N") (class "Default")
      (node (ref "IC1") (pin "16") (pinfunction "USBDM_16") (pintype "bidirectional"))
      (node (ref "U$1") (pin "2_D-") (pinfunction "D-_2_D-") (pintype "bidirectional"))
    )
    (net (code "85") (name "/USBD_P") (class "Default")
      (node (ref "IC1") (pin "15") (pinfunction "USBDP_15") (pintype "bidirectional"))
      (node (ref "U$1") (pin "3_D+") (pinfunction "D+_3_D+") (pintype "bidirectional"))
    )
    (net (code "86") (name "/XCLK") (class "Default")
      (node (ref "U5") (pin "16") (pinfunction "AN3_16") (pintype "bidirectional"))
    )
    (net (code "87") (name "/XRTS") (class "Default")
      (node (ref "U5") (pin "15") (pinfunction "AN2_15") (pintype "bidirectional"))
    )
    (net (code "88") (name "FAN_NEG") (class "Default")
      (node (ref "J2") (pin "P2") (pinfunction "2_P2") (pintype "bidirectional"))
      (node (ref "Q1") (pin "TAG") (pinfunction "D_TAG") (pintype "passive"))
      (node (ref "R10") (pin "2") (pinfunction "P$2_2") (pintype "passive"))
      (node (ref "R5") (pin "2") (pinfunction "P$2_2") (pintype "passive"))
      (node (ref "R6") (pin "2") (pinfunction "P$2_2") (pintype "passive"))
      (node (ref "R7") (pin "2") (pinfunction "P$2_2") (pintype "passive"))
      (node (ref "R8") (pin "2") (pinfunction "P$2_2") (pintype "passive"))
      (node (ref "R9") (pin "2") (pinfunction "P$2_2") (pintype "passive"))
    )
    (net (code "89") (name "FC_A") (class "Default")
      (node (ref "Q1") (pin "P1") (pinfunction "G_P1") (pintype "passive"))
      (node (ref "R11") (pin "2") (pinfunction "P$2_2") (pintype "passive"))
      (node (ref "U4") (pin "P$6") (pinfunction "P5.4_P$6") (pintype "bidirectional"))
    )
    (net (code "90") (name "FC_B") (class "Default")
      (node (ref "Q2") (pin "P1") (pinfunction "G_P1") (pintype "passive"))
      (node (ref "R12") (pin "2") (pinfunction "P$2_2") (pintype "passive"))
      (node (ref "U4") (pin "P$7") (pinfunction "P5.5_P$7") (pintype "bidirectional"))
    )
    (net (code "91") (name "FC_C") (class "Default")
      (node (ref "Q3") (pin "P1") (pinfunction "G_P1") (pintype "passive"))
      (node (ref "R13") (pin "2") (pinfunction "P$2_2") (pintype "passive"))
      (node (ref "U4") (pin "P$8") (pinfunction "P5.6_P$8") (pintype "bidirectional"))
    )
    (net (code "92") (name "GND") (class "Default")
      (node (ref "ANT1") (pin "P$2") (pinfunction "RFGND_P$2") (pintype "bidirectional"))
      (node (ref "ANT1") (pin "P$3") (pinfunction "RFGND_P$3") (pintype "bidirectional"))
      (node (ref "BLE1") (pin "P$13") (pinfunction "GND1_P$13") (pintype "power_in"))
      (node (ref "BLE1") (pin "P$14") (pinfunction "GND2_P$14") (pintype "power_in"))
      (node (ref "BLE1") (pin "P$21") (pinfunction "GND3_P$21") (pintype "power_in"))
      (node (ref "BLE1") (pin "P$22") (pinfunction "GND4_P$22") (pintype "power_in"))
      (node (ref "C1") (pin "1") (pinfunction "P$1_1") (pintype "passive"))
      (node (ref "C10") (pin "1") (pinfunction "P$1_1") (pintype "passive"))
      (node (ref "C11") (pin "1") (pinfunction "P$1_1") (pintype "passive"))
      (node (ref "C12") (pin "1") (pinfunction "P$1_1") (pintype "passive"))
      (node (ref "C13") (pin "1") (pinfunction "P$1_1") (pintype "passive"))
      (node (ref "C2") (pin "1") (pinfunction "P$1_1") (pintype "passive"))
      (node (ref "C3") (pin "1") (pinfunction "P$1_1") (pintype "passive"))
      (node (ref "C4") (pin "1") (pinfunction "P$1_1") (pintype "passive"))
      (node (ref "C5") (pin "1") (pinfunction "P$1_1") (pintype "passive"))
      (node (ref "C6") (pin "1") (pinfunction "P$1_1") (pintype "passive"))
      (node (ref "C7") (pin "1") (pinfunction "P$1_1") (pintype "passive"))
      (node (ref "C8") (pin "1") (pinfunction "P$1_1") (pintype "passive"))
      (node (ref "C9") (pin "1") (pinfunction "P$1_1") (pintype "passive"))
      (node (ref "IC1") (pin "18") (pinfunction "GND_18") (pintype "power_in"))
      (node (ref "IC1") (pin "21") (pinfunction "GND_21") (pintype "power_in"))
      (node (ref "IC1") (pin "25") (pinfunction "GND_25") (pintype "power_in"))
      (node (ref "IC1") (pin "26") (pinfunction "TEST_26") (pintype "input"))
      (node (ref "IC1") (pin "7") (pinfunction "GND_7") (pintype "power_in"))
      (node (ref "J1") (pin "P5") (pinfunction "5_P5") (pintype "bidirectional"))
      (node (ref "J10") (pin "P3") (pinfunction "GND_P3") (pintype "bidirectional"))
      (node (ref "J11") (pin "P13") (pinfunction "13_P13") (pintype "bidirectional"))
      (node (ref "J11") (pin "P2") (pinfunction "2_P2") (pintype "bidirectional"))
      (node (ref "J12") (pin "GND") (pinfunction "GND_GND") (pintype "bidirectional"))
      (node (ref "J13") (pin "P12") (pinfunction "12_P12") (pintype "bidirectional"))
      (node (ref "J13") (pin "P2") (pinfunction "2_P2") (pintype "bidirectional"))
      (node (ref "J3") (pin "P2") (pinfunction "2_P2") (pintype "bidirectional"))
      (node (ref "J4") (pin "P2") (pinfunction "2_P2") (pintype "bidirectional"))
      (node (ref "J5") (pin "P2") (pinfunction "2_P2") (pintype "bidirectional"))
      (node (ref "J7") (pin "GND") (pinfunction "GND_GND") (pintype "bidirectional"))
      (node (ref "J9") (pin "P2") (pinfunction "2_P2") (pintype "bidirectional"))
      (node (ref "Q1") (pin "P3") (pinfunction "S_P3") (pintype "passive"))
      (node (ref "Q2") (pin "P3") (pinfunction "S_P3") (pintype "passive"))
      (node (ref "Q3") (pin "P3") (pinfunction "S_P3") (pintype "passive"))
      (node (ref "Q4") (pin "P3") (pinfunction "S_P3") (pintype "passive"))
      (node (ref "Q5") (pin "P3") (pinfunction "S_P3") (pintype "passive"))
      (node (ref "R11") (pin "1") (pinfunction "P$1_1") (pintype "passive"))
      (node (ref "R12") (pin "1") (pinfunction "P$1_1") (pintype "passive"))
      (node (ref "R13") (pin "1") (pinfunction "P$1_1") (pintype "passive"))
      (node (ref "R14") (pin "1") (pinfunction "P$1_1") (pintype "passive"))
      (node (ref "R2") (pin "1") (pinfunction "P$1_1") (pintype "passive"))
      (node (ref "R22") (pin "1") (pinfunction "P$1_1") (pintype "passive"))
      (node (ref "R3") (pin "1") (pinfunction "P$1_1") (pintype "passive"))
      (node (ref "U$1") (pin "4_GND") (pinfunction "GND_4_GND") (pintype "bidirectional"))
      (node (ref "U1") (pin "16") (pinfunction "AVSS_16") (pintype "bidirectional"))
      (node (ref "U1") (pin "29") (pinfunction "VSS_29") (pintype "bidirectional"))
      (node (ref "U1") (pin "39") (pinfunction "VSS_39") (pintype "bidirectional"))
      (node (ref "U1") (pin "6") (pinfunction "DISVREG_6") (pintype "bidirectional"))
      (node (ref "U2") (pin "GND") (pinfunction "GND_GND") (pintype "power_in"))
      (node (ref "U3") (pin "P$19") (pinfunction "GND_P$19") (pintype "bidirectional"))
      (node (ref "U3") (pin "P$2") (pinfunction "GND_P$2") (pintype "bidirectional"))
      (node (ref "U3") (pin "P$22") (pinfunction "GND_P$22") (pintype "bidirectional"))
      (node (ref "U3") (pin "P$39") (pinfunction "GND_P$39") (pintype "bidirectional"))
      (node (ref "U4") (pin "P$1") (pinfunction "GND1_P$1") (pintype "bidirectional"))
      (node (ref "U4") (pin "P$18") (pinfunction "AGND_P$18") (pintype "bidirectional"))
      (node (ref "U4") (pin "P$35") (pinfunction "GND2_P$35") (pintype "bidirectional"))
      (node (ref "U4") (pin "P$42") (pinfunction "RFGND1_P$42") (pintype "bidirectional"))
      (node (ref "U4") (pin "P$44") (pinfunction "RFGND2_P$44") (pintype "bidirectional"))
      (node (ref "U4") (pin "P$52") (pinfunction "GND3_P$52") (pintype "bidirectional"))
      (node (ref "U5") (pin "12") (pinfunction "VREF-_12") (pintype "bidirectional"))
      (node (ref "U5") (pin "76") (pinfunction "GND_76") (pintype "bidirectional"))
    )
    (net (code "93") (name "HC") (class "Default")
      (node (ref "Q4") (pin "P1") (pinfunction "G_P1") (pintype "passive"))
      (node (ref "R14") (pin "2") (pinfunction "P$2_2") (pintype "passive"))
      (node (ref "U1") (pin "2") (pinfunction "RP22/PMA1/CN18/RC6_2") (pintype "bidirectional"))
      (node (ref "U5") (pin "60") (pinfunction "GP12_60") (pintype "bidirectional"))
    )
    (net (code "94") (name "HEAT_NEG") (class "Default")
      (node (ref "J6") (pin "P2") (pinfunction "2_P2") (pintype "bidirectional"))
      (node (ref "Q4") (pin "TAG") (pinfunction "D_TAG") (pintype "passive"))
    )
    (net (code "95") (name "LCD_EN") (class "Default")
      (node (ref "Q5") (pin "P1") (pinfunction "G_P1") (pintype "passive"))
      (node (ref "R3") (pin "2") (pinfunction "P$2_2") (pintype "passive"))
      (node (ref "U1") (pin "41") (pinfunction "CN27/USBID/RB5_41") (pintype "bidirectional"))
    )
    (net (code "96") (name "LCD_GND") (class "Default")
      (node (ref "J13") (pin "P11") (pinfunction "11_P11") (pintype "bidirectional"))
      (node (ref "Q5") (pin "TAG") (pinfunction "D_TAG") (pintype "passive"))
    )
    (net (code "97") (name "Net-(ANT1-RFOUT)") (class "Default")
      (node (ref "ANT1") (pin "P$1") (pinfunction "RFOUT_P$1") (pintype "bidirectional"))
      (node (ref "U4") (pin "P$43") (pinfunction "RFOUT_P$43") (pintype "bidirectional"))
    )
    (net (code "98") (name "Net-(C9-P$2)") (class "Default")
      (node (ref "C9") (pin "2") (pinfunction "P$2_2") (pintype "passive"))
      (node (ref "U1") (pin "7") (pinfunction "VCAP/VDDCORE_7") (pintype "bidirectional"))
    )
    (net (code "99") (name "Net-(IC1-~{RESET})") (class "Default")
      (node (ref "IC1") (pin "19") (pinfunction "~{RESET}_19") (pintype "input"))
      (node (ref "R22") (pin "2") (pinfunction "P$2_2") (pintype "passive"))
      (node (ref "R24") (pin "1") (pinfunction "P$1_1") (pintype "passive"))
    )
    (net (code "100") (name "Net-(Q2-D)") (class "Default")
      (node (ref "Q2") (pin "TAG") (pinfunction "D_TAG") (pintype "passive"))
      (node (ref "R5") (pin "1") (pinfunction "P$1_1") (pintype "passive"))
      (node (ref "R6") (pin "1") (pinfunction "P$1_1") (pintype "passive"))
      (node (ref "R9") (pin "1") (pinfunction "P$1_1") (pintype "passive"))
    )
    (net (code "101") (name "Net-(Q3-D)") (class "Default")
      (node (ref "Q3") (pin "TAG") (pinfunction "D_TAG") (pintype "passive"))
      (node (ref "R10") (pin "1") (pinfunction "P$1_1") (pintype "passive"))
      (node (ref "R7") (pin "1") (pinfunction "P$1_1") (pintype "passive"))
      (node (ref "R8") (pin "1") (pinfunction "P$1_1") (pintype "passive"))
    )
    (net (code "102") (name "Net-(R1-P$1)") (class "Default")
      (node (ref "R1") (pin "1") (pinfunction "P$1_1") (pintype "passive"))
      (node (ref "R2") (pin "2") (pinfunction "P$2_2") (pintype "passive"))
      (node (ref "U4") (pin "P$19") (pinfunction "ADC0_P$19") (pintype "bidirectional"))
    )
    (net (code "103") (name "Net-(R16-P$1)") (class "Default")
      (node (ref "R16") (pin "1") (pinfunction "P$1_1") (pintype "passive"))
      (node (ref "U4") (pin "P$65") (pinfunction "LED1_P$65") (pintype "bidirectional"))
    )
    (net (code "104") (name "Net-(R16-P$2)") (class "Default")
      (node (ref "D1") (pin "C") (pinfunction "C_C") (pintype "passive"))
      (node (ref "R16") (pin "2") (pinfunction "P$2_2") (pintype "passive"))
    )
    (net (code "105") (name "Net-(R17-P$1)") (class "Default")
      (node (ref "R17") (pin "1") (pinfunction "P$1_1") (pintype "passive"))
      (node (ref "U4") (pin "P$66") (pinfunction "LED2_P$66") (pintype "bidirectional"))
    )
    (net (code "106") (name "Net-(R17-P$2)") (class "Default")
      (node (ref "D2") (pin "C") (pinfunction "C_C") (pintype "passive"))
      (node (ref "R17") (pin "2") (pinfunction "P$2_2") (pintype "passive"))
    )
    (net (code "107") (name "Net-(R18-P$1)") (class "Default")
      (node (ref "R18") (pin "1") (pinfunction "P$1_1") (pintype "passive"))
      (node (ref "U4") (pin "P$67") (pinfunction "LED3_P$67") (pintype "bidirectional"))
    )
    (net (code "108") (name "Net-(R18-P$2)") (class "Default")
      (node (ref "D3") (pin "C") (pinfunction "C_C") (pintype "passive"))
      (node (ref "R18") (pin "2") (pinfunction "P$2_2") (pintype "passive"))
    )
    (net (code "109") (name "Net-(R20-P$2)") (class "Default")
      (node (ref "D4") (pin "C") (pinfunction "C_C") (pintype "passive"))
      (node (ref "R20") (pin "2") (pinfunction "P$2_2") (pintype "passive"))
    )
    (net (code "110") (name "Net-(R21-P$2)") (class "Default")
      (node (ref "D5") (pin "C") (pinfunction "C_C") (pintype "passive"))
      (node (ref "R21") (pin "2") (pinfunction "P$2_2") (pintype "passive"))
    )
    (net (code "111") (name "Net-(R25-P$2)") (class "Default")
      (node (ref "R25") (pin "2") (pinfunction "P$2_2") (pintype "passive"))
      (node (ref "U3") (pin "P$16") (pinfunction "LCD_SDO_P$16") (pintype "bidirectional"))
    )
    (net (code "112") (name "Net-(U5-TCK)") (class "Default")
      (node (ref "J7") (pin "TCK") (pinfunction "TCK_TCK") (pintype "bidirectional"))
      (node (ref "U5") (pin "79") (pinfunction "TCK_79") (pintype "bidirectional"))
    )
    (net (code "113") (name "Net-(U5-TDI)") (class "Default")
      (node (ref "J7") (pin "TDI") (pinfunction "TDI_TDI") (pintype "bidirectional"))
      (node (ref "U5") (pin "78") (pinfunction "TDI_78") (pintype "bidirectional"))
    )
    (net (code "114") (name "Net-(U5-TDO)") (class "Default")
      (node (ref "J7") (pin "TDO") (pinfunction "TDO_TDO") (pintype "bidirectional"))
      (node (ref "U5") (pin "77") (pinfunction "TDO_77") (pintype "bidirectional"))
    )
    (net (code "115") (name "Net-(U5-TMS)") (class "Default")
      (node (ref "J7") (pin "TMS") (pinfunction "TMS_TMS") (pintype "bidirectional"))
      (node (ref "U5") (pin "80") (pinfunction "TMS_80") (pintype "bidirectional"))
    )
    (net (code "116") (name "unconnected-(BLE1-NC1-PadP$5)") (class "Default")
      (node (ref "BLE1") (pin "P$5") (pinfunction "NC1_P$5") (pintype "no_connect"))
    )
    (net (code "117") (name "unconnected-(BLE1-NC2-PadP$6)") (class "Default")
      (node (ref "BLE1") (pin "P$6") (pinfunction "NC2_P$6") (pintype "no_connect"))
    )
    (net (code "118") (name "unconnected-(BLE1-NC3-PadP$7)") (class "Default")
      (node (ref "BLE1") (pin "P$7") (pinfunction "NC3_P$7") (pintype "no_connect"))
    )
    (net (code "119") (name "unconnected-(BLE1-NC4-PadP$8)") (class "Default")
      (node (ref "BLE1") (pin "P$8") (pinfunction "NC4_P$8") (pintype "no_connect"))
    )
    (net (code "120") (name "unconnected-(BLE1-NC5-PadP$9)") (class "Default")
      (node (ref "BLE1") (pin "P$9") (pinfunction "NC5_P$9") (pintype "no_connect"))
    )
    (net (code "121") (name "unconnected-(BLE1-NC6-PadP$10)") (class "Default")
      (node (ref "BLE1") (pin "P$10") (pinfunction "NC6_P$10") (pintype "no_connect"))
    )
    (net (code "122") (name "unconnected-(BLE1-NC7-PadP$16)") (class "Default")
      (node (ref "BLE1") (pin "P$16") (pinfunction "NC7_P$16") (pintype "no_connect"))
    )
    (net (code "123") (name "unconnected-(BLE1-NC8-PadP$17)") (class "Default")
      (node (ref "BLE1") (pin "P$17") (pinfunction "NC8_P$17") (pintype "no_connect"))
    )
    (net (code "124") (name "unconnected-(BLE1-NC9-PadP$18)") (class "Default")
      (node (ref "BLE1") (pin "P$18") (pinfunction "NC9_P$18") (pintype "no_connect"))
    )
    (net (code "125") (name "unconnected-(BLE1-NC10-PadP$19)") (class "Default")
      (node (ref "BLE1") (pin "P$19") (pinfunction "NC10_P$19") (pintype "no_connect"))
    )
    (net (code "126") (name "unconnected-(BLE1-PIO1-PadP$24)") (class "Default")
      (node (ref "BLE1") (pin "P$24") (pinfunction "PIO1_P$24") (pintype "bidirectional"))
    )
    (net (code "127") (name "unconnected-(BLE1-PIO2-PadP$25)") (class "Default")
      (node (ref "BLE1") (pin "P$25") (pinfunction "PIO2_P$25") (pintype "bidirectional"))
    )
    (net (code "128") (name "unconnected-(BLE1-PIO3-PadP$26)") (class "Default")
      (node (ref "BLE1") (pin "P$26") (pinfunction "PIO3_P$26") (pintype "bidirectional"))
    )
    (net (code "129") (name "unconnected-(BLE1-PIO5-PadP$28)") (class "Default")
      (node (ref "BLE1") (pin "P$28") (pinfunction "PIO5_P$28") (pintype "bidirectional"))
    )
    (net (code "130") (name "unconnected-(BLE1-PIO6-PadP$29)") (class "Default")
      (node (ref "BLE1") (pin "P$29") (pinfunction "PIO6_P$29") (pintype "bidirectional"))
    )
    (net (code "131") (name "unconnected-(BLE1-PIO7-PadP$30)") (class "Default")
      (node (ref "BLE1") (pin "P$30") (pinfunction "PIO7_P$30") (pintype "bidirectional"))
    )
    (net (code "132") (name "unconnected-(BLE1-PIO8-PadP$31)") (class "Default")
      (node (ref "BLE1") (pin "P$31") (pinfunction "PIO8_P$31") (pintype "bidirectional"))
    )
    (net (code "133") (name "unconnected-(BLE1-PIO9-PadP$32)") (class "Default")
      (node (ref "BLE1") (pin "P$32") (pinfunction "PIO9_P$32") (pintype "bidirectional"))
    )
    (net (code "134") (name "unconnected-(BLE1-PIO10-PadP$33)") (class "Default")
      (node (ref "BLE1") (pin "P$33") (pinfunction "PIO10_P$33") (pintype "bidirectional"))
    )
    (net (code "135") (name "unconnected-(BLE1-PIO11-PadP$34)") (class "Default")
      (node (ref "BLE1") (pin "P$34") (pinfunction "PIO11_P$34") (pintype "bidirectional"))
    )
    (net (code "136") (name "unconnected-(BLE1-UB_D+-PadP$20)") (class "Default")
      (node (ref "BLE1") (pin "P$20") (pinfunction "UB_D+_P$20") (pintype "bidirectional"))
    )
    (net (code "137") (name "unconnected-(BLE1-USB_D--PadP$15)") (class "Default")
      (node (ref "BLE1") (pin "P$15") (pinfunction "USB_D-_P$15") (pintype "bidirectional"))
    )
    (net (code "138") (name "unconnected-(IC1-3V3OUT-Pad17)") (class "Default")
      (node (ref "IC1") (pin "17") (pinfunction "3V3OUT_17") (pintype "output"))
    )
    (net (code "139") (name "unconnected-(IC1-CBUS2-Pad13)") (class "Default")
      (node (ref "IC1") (pin "13") (pinfunction "CBUS2_13") (pintype "bidirectional"))
    )
    (net (code "140") (name "unconnected-(IC1-CBUS3-Pad14)") (class "Default")
      (node (ref "IC1") (pin "14") (pinfunction "CBUS3_14") (pintype "bidirectional"))
    )
    (net (code "141") (name "unconnected-(IC1-CBUS4-Pad12)") (class "Default")
      (node (ref "IC1") (pin "12") (pinfunction "CBUS4_12") (pintype "bidirectional"))
    )
    (net (code "142") (name "unconnected-(IC1-OSCI-Pad27)") (class "Default")
      (node (ref "IC1") (pin "27") (pinfunction "OSCI_27") (pintype "input"))
    )
    (net (code "143") (name "unconnected-(IC1-OSCO-Pad28)") (class "Default")
      (node (ref "IC1") (pin "28") (pinfunction "OSCO_28") (pintype "output"))
    )
    (net (code "144") (name "unconnected-(IC1-~{DCD}-Pad10)") (class "Default")
      (node (ref "IC1") (pin "10") (pinfunction "~{DCD}_10") (pintype "input"))
    )
    (net (code "145") (name "unconnected-(IC1-~{DSR}-Pad9)") (class "Default")
      (node (ref "IC1") (pin "9") (pinfunction "~{DSR}_9") (pintype "input"))
    )
    (net (code "146") (name "unconnected-(IC1-~{DTR}-Pad2)") (class "Default")
      (node (ref "IC1") (pin "2") (pinfunction "~{DTR}_2") (pintype "output"))
    )
    (net (code "147") (name "unconnected-(IC1-~{RI}-Pad6)") (class "Default")
      (node (ref "IC1") (pin "6") (pinfunction "~{RI}_6") (pintype "input"))
    )
    (net (code "148") (name "unconnected-(J1-3-PadP3)") (class "Default")
      (node (ref "J1") (pin "P3") (pinfunction "3_P3") (pintype "bidirectional"))
    )
    (net (code "149") (name "unconnected-(J10-LVP-PadP6)") (class "Default")
      (node (ref "J10") (pin "P6") (pinfunction "LVP_P6") (pintype "bidirectional"))
    )
    (net (code "150") (name "unconnected-(U$1-PadSHIELD1)") (class "Default")
      (node (ref "U$1") (pin "SHIELD1") (pinfunction "SHIELD1_SHIELD1") (pintype "bidirectional"))
    )
    (net (code "151") (name "unconnected-(U$1-PadSHIELD2)") (class "Default")
      (node (ref "U$1") (pin "SHIELD2") (pinfunction "SHIELD2_SHIELD2") (pintype "bidirectional"))
    )
    (net (code "152") (name "unconnected-(U1-RP24{slash}PMA5{slash}CN20{slash}RC8-Pad4)") (class "Default")
      (node (ref "U1") (pin "4") (pinfunction "RP24/PMA5/CN20/RC8_4") (pintype "bidirectional"))
    )
    (net (code "153") (name "unconnected-(U3-3V3_IN-PadP$20)") (class "Default")
      (node (ref "U3") (pin "P$20") (pinfunction "3V3_IN_P$20") (pintype "bidirectional"))
    )
    (net (code "154") (name "unconnected-(U3-3V3_OUT-PadP$40)") (class "Default")
      (node (ref "U3") (pin "P$40") (pinfunction "3V3_OUT_P$40") (pintype "bidirectional"))
    )
    (net (code "155") (name "unconnected-(U3-5V_IN-PadP$1)") (class "Default")
      (node (ref "U3") (pin "P$1") (pinfunction "5V_IN_P$1") (pintype "bidirectional"))
    )
    (net (code "156") (name "unconnected-(U3-BL_CTL-PadP$21)") (class "Default")
      (node (ref "U3") (pin "P$21") (pinfunction "BL_CTL_P$21") (pintype "bidirectional"))
    )
    (net (code "157") (name "unconnected-(U3-NC-PadP$18)") (class "Default")
      (node (ref "U3") (pin "P$18") (pinfunction "NC_P$18") (pintype "bidirectional"))
    )
    (net (code "158") (name "unconnected-(U3-NC-PadP$23)") (class "Default")
      (node (ref "U3") (pin "P$23") (pinfunction "NC_P$23") (pintype "bidirectional"))
    )
    (net (code "159") (name "unconnected-(U3-NC-PadP$24)") (class "Default")
      (node (ref "U3") (pin "P$24") (pinfunction "NC_P$24") (pintype "bidirectional"))
    )
    (net (code "160") (name "unconnected-(U3-NC-PadP$30)") (class "Default")
      (node (ref "U3") (pin "P$30") (pinfunction "NC_P$30") (pintype "bidirectional"))
    )
    (net (code "161") (name "unconnected-(U4-ATEST1-PadP$46)") (class "Default")
      (node (ref "U4") (pin "P$46") (pinfunction "ATEST1_P$46") (pintype "bidirectional"))
    )
    (net (code "162") (name "unconnected-(U4-ATEST2-PadP$47)") (class "Default")
      (node (ref "U4") (pin "P$47") (pinfunction "ATEST2_P$47") (pintype "bidirectional"))
    )
    (net (code "163") (name "unconnected-(U4-FLASH_CS-PadP$36)") (class "Default")
      (node (ref "U4") (pin "P$36") (pinfunction "FLASH_CS_P$36") (pintype "bidirectional"))
    )
    (net (code "164") (name "unconnected-(U4-I2C0{slash}~{SPI0}-PadP$53)") (class "Default")
      (node (ref "U4") (pin "P$53") (pinfunction "I2C0/~{SPI0}_P$53") (pintype "bidirectional"))
    )
    (net (code "165") (name "unconnected-(U4-MISO0-PadP$57)") (class "Default")
      (node (ref "U4") (pin "P$57") (pinfunction "MISO0_P$57") (pintype "bidirectional"))
    )
    (net (code "166") (name "unconnected-(U4-MOSI0{slash}SDA-PadP$56)") (class "Default")
      (node (ref "U4") (pin "P$56") (pinfunction "MOSI0/SDA_P$56") (pintype "bidirectional"))
    )
    (net (code "167") (name "unconnected-(U4-ONEWIRE-PadP$54)") (class "Default")
      (node (ref "U4") (pin "P$54") (pinfunction "ONEWIRE_P$54") (pintype "bidirectional"))
    )
    (net (code "168") (name "unconnected-(U4-P2.1-PadP$39)") (class "Default")
      (node (ref "U4") (pin "P$39") (pinfunction "P2.1_P$39") (pintype "bidirectional"))
    )
    (net (code "169") (name "unconnected-(U4-P2.3-PadP$40)") (class "Default")
      (node (ref "U4") (pin "P$40") (pinfunction "P2.3_P$40") (pintype "bidirectional"))
    )
    (net (code "170") (name "unconnected-(U4-P2.6-PadP$41)") (class "Default")
      (node (ref "U4") (pin "P$41") (pinfunction "P2.6_P$41") (pintype "bidirectional"))
    )
    (net (code "171") (name "unconnected-(U4-P5.0-PadP$2)") (class "Default")
      (node (ref "U4") (pin "P$2") (pinfunction "P5.0_P$2") (pintype "bidirectional"))
    )
    (net (code "172") (name "unconnected-(U4-P5.1-PadP$3)") (class "Default")
      (node (ref "U4") (pin "P$3") (pinfunction "P5.1_P$3") (pintype "bidirectional"))
    )
    (net (code "173") (name "unconnected-(U4-P5.2-PadP$4)") (class "Default")
      (node (ref "U4") (pin "P$4") (pinfunction "P5.2_P$4") (pintype "bidirectional"))
    )
    (net (code "174") (name "unconnected-(U4-P5.7-PadP$9)") (class "Default")
      (node (ref "U4") (pin "P$9") (pinfunction "P5.7_P$9") (pintype "bidirectional"))
    )
    (net (code "175") (name "unconnected-(U4-RADIO_CCA-PadP$49)") (class "Default")
      (node (ref "U4") (pin "P$49") (pinfunction "RADIO_CCA_P$49") (pintype "bidirectional"))
    )
    (net (code "176") (name "unconnected-(U4-RADIO_CS-PadP$48)") (class "Default")
      (node (ref "U4") (pin "P$48") (pinfunction "RADIO_CS_P$48") (pintype "bidirectional"))
    )
    (net (code "177") (name "unconnected-(U4-RADIO_SFD-PadP$50)") (class "Default")
      (node (ref "U4") (pin "P$50") (pinfunction "RADIO_SFD_P$50") (pintype "bidirectional"))
    )
    (net (code "178") (name "unconnected-(U4-RFTXRX-PadP$45)") (class "Default")
      (node (ref "U4") (pin "P$45") (pinfunction "RFTXRX_P$45") (pintype "bidirectional"))
    )
    (net (code "179") (name "unconnected-(U4-SCLK0{slash}SCL-PadP$58)") (class "Default")
      (node (ref "U4") (pin "P$58") (pinfunction "SCLK0/SCL_P$58") (pintype "bidirectional"))
    )
    (net (code "180") (name "unconnected-(U4-STE0-PadP$55)") (class "Default")
      (node (ref "U4") (pin "P$55") (pinfunction "STE0_P$55") (pintype "bidirectional"))
    )
    (net (code "181") (name "unconnected-(U4-UART0RX-PadP$60)") (class "Default")
      (node (ref "U4") (pin "P$60") (pinfunction "UART0RX_P$60") (pintype "bidirectional"))
    )
    (net (code "182") (name "unconnected-(U4-UART0TX-PadP$59)") (class "Default")
      (node (ref "U4") (pin "P$59") (pinfunction "UART0TX_P$59") (pintype "bidirectional"))
    )
    (net (code "183") (name "unconnected-(U4-VEREF+-PadP$28)") (class "Default")
      (node (ref "U4") (pin "P$28") (pinfunction "VEREF+_P$28") (pintype "bidirectional"))
    )
    (net (code "184") (name "unconnected-(U4-VEREF--PadP$29)") (class "Default")
      (node (ref "U4") (pin "P$29") (pinfunction "VEREF-_P$29") (pintype "bidirectional"))
    )
    (net (code "185") (name "unconnected-(U4-VREF+-PadP$27)") (class "Default")
      (node (ref "U4") (pin "P$27") (pinfunction "VREF+_P$27") (pintype "bidirectional"))
    )
    (net (code "186") (name "unconnected-(U4-XOSC16IN-PadP$64)") (class "Default")
      (node (ref "U4") (pin "P$64") (pinfunction "XOSC16IN_P$64") (pintype "bidirectional"))
    )
    (net (code "187") (name "unconnected-(U4-XOSC16OUT-PadP$63)") (class "Default")
      (node (ref "U4") (pin "P$63") (pinfunction "XOSC16OUT_P$63") (pintype "bidirectional"))
    )
    (net (code "188") (name "unconnected-(U4-XT2IN-PadP$11)") (class "Default")
      (node (ref "U4") (pin "P$11") (pinfunction "XT2IN_P$11") (pintype "bidirectional"))
    )
    (net (code "189") (name "unconnected-(U4-XT2OUT-PadP$10)") (class "Default")
      (node (ref "U4") (pin "P$10") (pinfunction "XT2OUT_P$10") (pintype "bidirectional"))
    )
    (net (code "190") (name "unconnected-(U5-BL_CLK-Pad25)") (class "Default")
      (node (ref "U5") (pin "25") (pinfunction "BL_CLK_25") (pintype "bidirectional"))
    )
    (net (code "191") (name "unconnected-(U5-BL_CTS-Pad23)") (class "Default")
      (node (ref "U5") (pin "23") (pinfunction "BL_CTS_23") (pintype "bidirectional"))
    )
    (net (code "192") (name "unconnected-(U5-BL_RX-Pad21)") (class "Default")
      (node (ref "U5") (pin "21") (pinfunction "BL_RX_21") (pintype "bidirectional"))
    )
    (net (code "193") (name "unconnected-(U5-BL_SEL-Pad24)") (class "Default")
      (node (ref "U5") (pin "24") (pinfunction "BL_SEL_24") (pintype "bidirectional"))
    )
    (net (code "194") (name "unconnected-(U5-BL_TX-Pad22)") (class "Default")
      (node (ref "U5") (pin "22") (pinfunction "BL_TX_22") (pintype "bidirectional"))
    )
    (net (code "195") (name "unconnected-(U5-BUCK_~{LDO}-Pad47)") (class "Default")
      (node (ref "U5") (pin "47") (pinfunction "BUCK_~{LDO}_47") (pintype "bidirectional"))
    )
    (net (code "196") (name "unconnected-(U5-DVDD-Pad44)") (class "Default")
      (node (ref "U5") (pin "44") (pinfunction "DVDD_44") (pintype "bidirectional"))
    )
    (net (code "197") (name "unconnected-(U5-EXT_ANT-Pad69)") (class "Default")
      (node (ref "U5") (pin "69") (pinfunction "EXT_ANT_69") (pintype "bidirectional"))
    )
    (net (code "198") (name "unconnected-(U5-GND-Pad26)") (class "Default")
      (node (ref "U5") (pin "26") (pinfunction "GND_26") (pintype "bidirectional"))
    )
    (net (code "199") (name "unconnected-(U5-GND-Pad41)") (class "Default")
      (node (ref "U5") (pin "41") (pinfunction "GND_41") (pintype "bidirectional"))
    )
    (net (code "200") (name "unconnected-(U5-GP0-Pad75)") (class "Default")
      (node (ref "U5") (pin "75") (pinfunction "GP0_75") (pintype "bidirectional"))
    )
    (net (code "201") (name "unconnected-(U5-GP2-Pad73)") (class "Default")
      (node (ref "U5") (pin "73") (pinfunction "GP2_73") (pintype "bidirectional"))
    )
    (net (code "202") (name "unconnected-(U5-GP3-Pad72)") (class "Default")
      (node (ref "U5") (pin "72") (pinfunction "GP3_72") (pintype "bidirectional"))
    )
    (net (code "203") (name "unconnected-(U5-GP4-Pad71)") (class "Default")
      (node (ref "U5") (pin "71") (pinfunction "GP4_71") (pintype "bidirectional"))
    )
    (net (code "204") (name "unconnected-(U5-GP6-Pad66)") (class "Default")
      (node (ref "U5") (pin "66") (pinfunction "GP6_66") (pintype "bidirectional"))
    )
    (net (code "205") (name "unconnected-(U5-GP7-Pad65)") (class "Default")
      (node (ref "U5") (pin "65") (pinfunction "GP7_65") (pintype "bidirectional"))
    )
    (net (code "206") (name "unconnected-(U5-GP8-Pad64)") (class "Default")
      (node (ref "U5") (pin "64") (pinfunction "GP8_64") (pintype "bidirectional"))
    )
    (net (code "207") (name "unconnected-(U5-GP9-Pad63)") (class "Default")
      (node (ref "U5") (pin "63") (pinfunction "GP9_63") (pintype "bidirectional"))
    )
    (net (code "208") (name "unconnected-(U5-GP13-Pad59)") (class "Default")
      (node (ref "U5") (pin "59") (pinfunction "GP13_59") (pintype "bidirectional"))
    )
    (net (code "209") (name "unconnected-(U5-INT1-Pad7)") (class "Default")
      (node (ref "U5") (pin "7") (pinfunction "INT1_7") (pintype "bidirectional"))
    )
    (net (code "210") (name "unconnected-(U5-PWM0-Pad8)") (class "Default")
      (node (ref "U5") (pin "8") (pinfunction "PWM0_8") (pintype "bidirectional"))
    )
    (net (code "211") (name "unconnected-(U5-RF_GND-Pad68)") (class "Default")
      (node (ref "U5") (pin "68") (pinfunction "RF_GND_68") (pintype "bidirectional"))
    )
    (net (code "212") (name "unconnected-(U5-RF_GND-Pad70)") (class "Default")
      (node (ref "U5") (pin "70") (pinfunction "RF_GND_70") (pintype "bidirectional"))
    )
    (net (code "213") (name "unconnected-(U5-SPI_CS2-Pad1)") (class "Default")
      (node (ref "U5") (pin "1") (pinfunction "SPI_CS2_1") (pintype "bidirectional"))
    )
    (net (code "214") (name "unconnected-(U5-TW1_CLK-Pad37)") (class "Default")
      (node (ref "U5") (pin "37") (pinfunction "TW1_CLK_37") (pintype "bidirectional"))
    )
    (net (code "215") (name "unconnected-(U5-TW1_DAT-Pad38)") (class "Default")
      (node (ref "U5") (pin "38") (pinfunction "TW1_DAT_38") (pintype "bidirectional"))
    )
    (net (code "216") (name "unconnected-(U5-U1_CLK-Pad31)") (class "Default")
      (node (ref "U5") (pin "31") (pinfunction "U1_CLK_31") (pintype "bidirectional"))
    )
    (net (code "217") (name "unconnected-(U5-U2_CTS-Pad34)") (class "Default")
      (node (ref "U5") (pin "34") (pinfunction "U2_CTS_34") (pintype "bidirectional"))
    )
    (net (code "218") (name "unconnected-(U5-USB_N-Pad42)") (class "Default")
      (node (ref "U5") (pin "42") (pinfunction "USB_N_42") (pintype "bidirectional"))
    )
    (net (code "219") (name "unconnected-(U5-USB_P-Pad43)") (class "Default")
      (node (ref "U5") (pin "43") (pinfunction "USB_P_43") (pintype "bidirectional"))
    )
    (net (code "220") (name "unconnected-(U5-VDDCORE-Pad45)") (class "Default")
      (node (ref "U5") (pin "45") (pinfunction "VDDCORE_45") (pintype "bidirectional"))
    )
    (net (code "221") (name "unconnected-(U5-VDDOUT-Pad46)") (class "Default")
      (node (ref "U5") (pin "46") (pinfunction "VDDOUT_46") (pintype "bidirectional"))
    )
    (net (code "222") (name "unconnected-(U5-VREF+-Pad19)") (class "Default")
      (node (ref "U5") (pin "19") (pinfunction "VREF+_19") (pintype "bidirectional"))
    )
    (net (code "223") (name "unconnected-(U5-~{RESET}-Pad20)") (class "Default")
      (node (ref "U5") (pin "20") (pinfunction "~{RESET}_20") (pintype "bidirectional"))
    )
  )
)
